# VSAB_75R_P.net
KiCad netlist of a schematic drawn in EAGLE
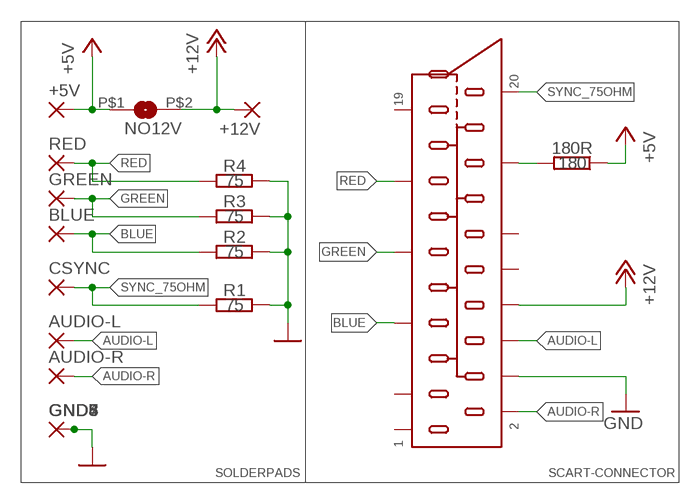
[diagram p0: schematic, sheet 1]

(export (version "E")
  (design (tool "Eeschema 10.0.6"))
  (components
    (comp (ref "+5V")
      (value "WIREPADSMD5-1,8")
      (footprint "eagle-import:5-1,8")
      (libsource (lib "eagle-import") (part "WIREPADSMD5-1,8"))
    )
    (comp (ref "+12V")
      (value "WIREPADSMD5-1,8")
      (footprint "eagle-import:5-1,8")
      (libsource (lib "eagle-import") (part "WIREPADSMD5-1,8"))
    )
    (comp (ref "180R")
      (value "180")
      (footprint "eagle-import:R0805")
      (libsource (lib "eagle-import") (part "R-EU_R0805"))
    )
    (comp (ref "AUDIO-L")
      (value "WIREPADSMD5-1,8")
      (footprint "eagle-import:5-1,8")
      (libsource (lib "eagle-import") (part "WIREPADSMD5-1,8"))
    )
    (comp (ref "AUDIO-R")
      (value "WIREPADSMD5-1,8")
      (footprint "eagle-import:5-1,8")
      (libsource (lib "eagle-import") (part "WIREPADSMD5-1,8"))
    )
    (comp (ref "BLUE")
      (value "WIREPADSMD5-1,8")
      (footprint "eagle-import:5-1,8")
      (libsource (lib "eagle-import") (part "WIREPADSMD5-1,8"))
    )
    (comp (ref "CSYNC")
      (value "WIREPADSMD5-1,8")
      (footprint "eagle-import:5-1,8")
      (libsource (lib "eagle-import") (part "WIREPADSMD5-1,8"))
    )
    (comp (ref "GND")
      (value "WIREPADSMD5-1,8")
      (footprint "eagle-import:5-1,8")
      (libsource (lib "eagle-import") (part "WIREPADSMD5-1,8"))
    )
    (comp (ref "GND3")
      (value "WIREPADSMD5-1,8")
      (footprint "eagle-import:5-1,8")
      (libsource (lib "eagle-import") (part "WIREPADSMD5-1,8"))
    )
    (comp (ref "GND4")
      (value "WIREPADSMD5-1,8")
      (footprint "eagle-import:5-1,8")
      (libsource (lib "eagle-import") (part "WIREPADSMD5-1,8"))
    )
    (comp (ref "GND5")
      (value "WIREPADSMD5-1,8")
      (footprint "eagle-import:5-1,8")
      (libsource (lib "eagle-import") (part "WIREPADSMD5-1,8"))
    )
    (comp (ref "GND6")
      (value "WIREPADSMD5-1,8")
      (footprint "eagle-import:5-1,8")
      (libsource (lib "eagle-import") (part "WIREPADSMD5-1,8"))
    )
    (comp (ref "GND7")
      (value "WIREPADSMD5-1,8")
      (footprint "eagle-import:5-1,8")
      (libsource (lib "eagle-import") (part "WIREPADSMD5-1,8"))
    )
    (comp (ref "GND8")
      (value "WIREPADSMD5-1,8")
      (footprint "eagle-import:5-1,8")
      (libsource (lib "eagle-import") (part "WIREPADSMD5-1,8"))
    )
    (comp (ref "GREEN")
      (value "WIREPADSMD5-1,8")
      (footprint "eagle-import:5-1,8")
      (libsource (lib "eagle-import") (part "WIREPADSMD5-1,8"))
    )
    (comp (ref "NO12V")
      (value "MY_JUMPER")
      (footprint "eagle-import:MYJUMP")
      (libsource (lib "eagle-import") (part "MY_JUMPER"))
    )
    (comp (ref "R1")
      (value "75")
      (footprint "eagle-import:R0805")
      (libsource (lib "eagle-import") (part "R-EU_R0805"))
    )
    (comp (ref "R2")
      (value "75")
      (footprint "eagle-import:R0805")
      (libsource (lib "eagle-import") (part "R-EU_R0805"))
    )
    (comp (ref "R3")
      (value "75")
      (footprint "eagle-import:R0805")
      (libsource (lib "eagle-import") (part "R-EU_R0805"))
    )
    (comp (ref "R4")
      (value "75")
      (footprint "eagle-import:R0805")
      (libsource (lib "eagle-import") (part "R-EU_R0805"))
    )
    (comp (ref "RED")
      (value "WIREPADSMD5-1,8")
      (footprint "eagle-import:5-1,8")
      (libsource (lib "eagle-import") (part "WIREPADSMD5-1,8"))
    )
    (comp (ref "U$2")
      (value "SCART_PLUG")
      (footprint "eagle-import:SCART")
      (libsource (lib "eagle-import") (part "SCART_PLUG"))
    )
  )
  (nets
    (net (code "1") (name "+5V") (class "Default")
      (node (ref "+5V") (pin "1") (pinfunction "P_1") (pintype "passive"))
      (node (ref "180R") (pin "1") (pinfunction "1_1") (pintype "passive"))
      (node (ref "NO12V") (pin "P$1") (pinfunction "1_P$1") (pintype "passive"))
    )
    (net (code "2") (name "+12V") (class "Default")
      (node (ref "+12V") (pin "1") (pinfunction "P_1") (pintype "passive"))
      (node (ref "NO12V") (pin "P$2") (pinfunction "2_P$2") (pintype "passive"))
      (node (ref "U$2") (pin "8") (pinfunction "TV/AV_SW_8") (pintype "bidirectional"))
    )
    (net (code "3") (name "AUDIO-L") (class "Default")
      (node (ref "AUDIO-L") (pin "1") (pinfunction "P_1") (pintype "passive"))
      (node (ref "U$2") (pin "6") (pinfunction "AUDIO_IN_L_6") (pintype "bidirectional"))
    )
    (net (code "4") (name "AUDIO-R") (class "Default")
      (node (ref "AUDIO-R") (pin "1") (pinfunction "P_1") (pintype "passive"))
      (node (ref "U$2") (pin "2") (pinfunction "AUDIO_IN_R_2") (pintype "bidirectional"))
    )
    (net (code "5") (name "BLUE") (class "Default")
      (node (ref "BLUE") (pin "1") (pinfunction "P_1") (pintype "passive"))
      (node (ref "R2") (pin "2") (pinfunction "2_2") (pintype "passive"))
      (node (ref "U$2") (pin "7") (pinfunction "RGB_BLUE/YUV_V/PB_7") (pintype "bidirectional"))
    )
    (net (code "6") (name "GND") (class "Default")
      (node (ref "GND") (pin "1") (pinfunction "P_1") (pintype "passive"))
      (node (ref "GND3") (pin "1") (pinfunction "P_1") (pintype "passive"))
      (node (ref "GND4") (pin "1") (pinfunction "P_1") (pintype "passive"))
      (node (ref "GND5") (pin "1") (pinfunction "P_1") (pintype "passive"))
      (node (ref "GND6") (pin "1") (pinfunction "P_1") (pintype "passive"))
      (node (ref "GND7") (pin "1") (pinfunction "P_1") (pintype "passive"))
      (node (ref "GND8") (pin "1") (pinfunction "P_1") (pintype "passive"))
      (node (ref "R1") (pin "1") (pinfunction "1_1") (pintype "passive"))
      (node (ref "R2") (pin "1") (pinfunction "1_1") (pintype "passive"))
      (node (ref "R3") (pin "1") (pinfunction "1_1") (pintype "passive"))
      (node (ref "R4") (pin "1") (pinfunction "1_1") (pintype "passive"))
      (node (ref "U$2") (pin "13") (pinfunction "GND_13") (pintype "bidirectional"))
      (node (ref "U$2") (pin "14") (pinfunction "GND_14") (pintype "bidirectional"))
      (node (ref "U$2") (pin "17") (pinfunction "GND_17") (pintype "bidirectional"))
      (node (ref "U$2") (pin "18") (pinfunction "GND_18") (pintype "bidirectional"))
      (node (ref "U$2") (pin "4") (pinfunction "GND_4") (pintype "bidirectional"))
      (node (ref "U$2") (pin "5") (pinfunction "GND_5") (pintype "bidirectional"))
      (node (ref "U$2") (pin "9") (pinfunction "GND_9") (pintype "bidirectional"))
    )
    (net (code "7") (name "GREEN") (class "Default")
      (node (ref "GREEN") (pin "1") (pinfunction "P_1") (pintype "passive"))
      (node (ref "R3") (pin "2") (pinfunction "2_2") (pintype "passive"))
      (node (ref "U$2") (pin "11") (pinfunction "RGB_GREEN/YUV-Y_11") (pintype "bidirectional"))
    )
    (net (code "8") (name "Net-(U$2-AV{slash}RGB_SW)") (class "Default")
      (node (ref "180R") (pin "2") (pinfunction "2_2") (pintype "passive"))
      (node (ref "U$2") (pin "16") (pinfunction "AV/RGB_SW_16") (pintype "bidirectional"))
    )
    (net (code "9") (name "RED") (class "Default")
      (node (ref "R4") (pin "2") (pinfunction "2_2") (pintype "passive"))
      (node (ref "RED") (pin "1") (pinfunction "P_1") (pintype "passive"))
      (node (ref "U$2") (pin "15") (pinfunction "RGB_RED/YUV-U/PR/CHROMA_15") (pintype "bidirectional"))
    )
    (net (code "10") (name "SYNC_75OHM") (class "Default")
      (node (ref "CSYNC") (pin "1") (pinfunction "P_1") (pintype "passive"))
      (node (ref "R1") (pin "2") (pinfunction "2_2") (pintype "passive"))
      (node (ref "U$2") (pin "20") (pinfunction "COMP/SYNC/LUMA_IN_20") (pintype "bidirectional"))
    )
    (net (code "11") (name "unconnected-(U$2-ADUIO_OUT_R-Pad1)") (class "Default")
      (node (ref "U$2") (pin "1") (pinfunction "ADUIO_OUT_R_1") (pintype "bidirectional"))
    )
    (net (code "12") (name "unconnected-(U$2-AUDIO_OUT_L-Pad3)") (class "Default")
      (node (ref "U$2") (pin "3") (pinfunction "AUDIO_OUT_L_3") (pintype "bidirectional"))
    )
    (net (code "13") (name "unconnected-(U$2-COMP{slash}SNYC{slash}LUMA_OUT-Pad19)") (class "Default")
      (node (ref "U$2") (pin "19") (pinfunction "COMP/SNYC/LUMA_OUT_19") (pintype "bidirectional"))
    )
    (net (code "14") (name "unconnected-(U$2-D2B_IN-Pad10)") (class "Default")
      (node (ref "U$2") (pin "10") (pinfunction "D2B_IN_10") (pintype "bidirectional"))
    )
    (net (code "15") (name "unconnected-(U$2-D2B_OUT-Pad12)") (class "Default")
      (node (ref "U$2") (pin "12") (pinfunction "D2B_OUT_12") (pintype "bidirectional"))
    )
  )
)
